# Version_2.net
KiCad netlist of a schematic drawn in EAGLE
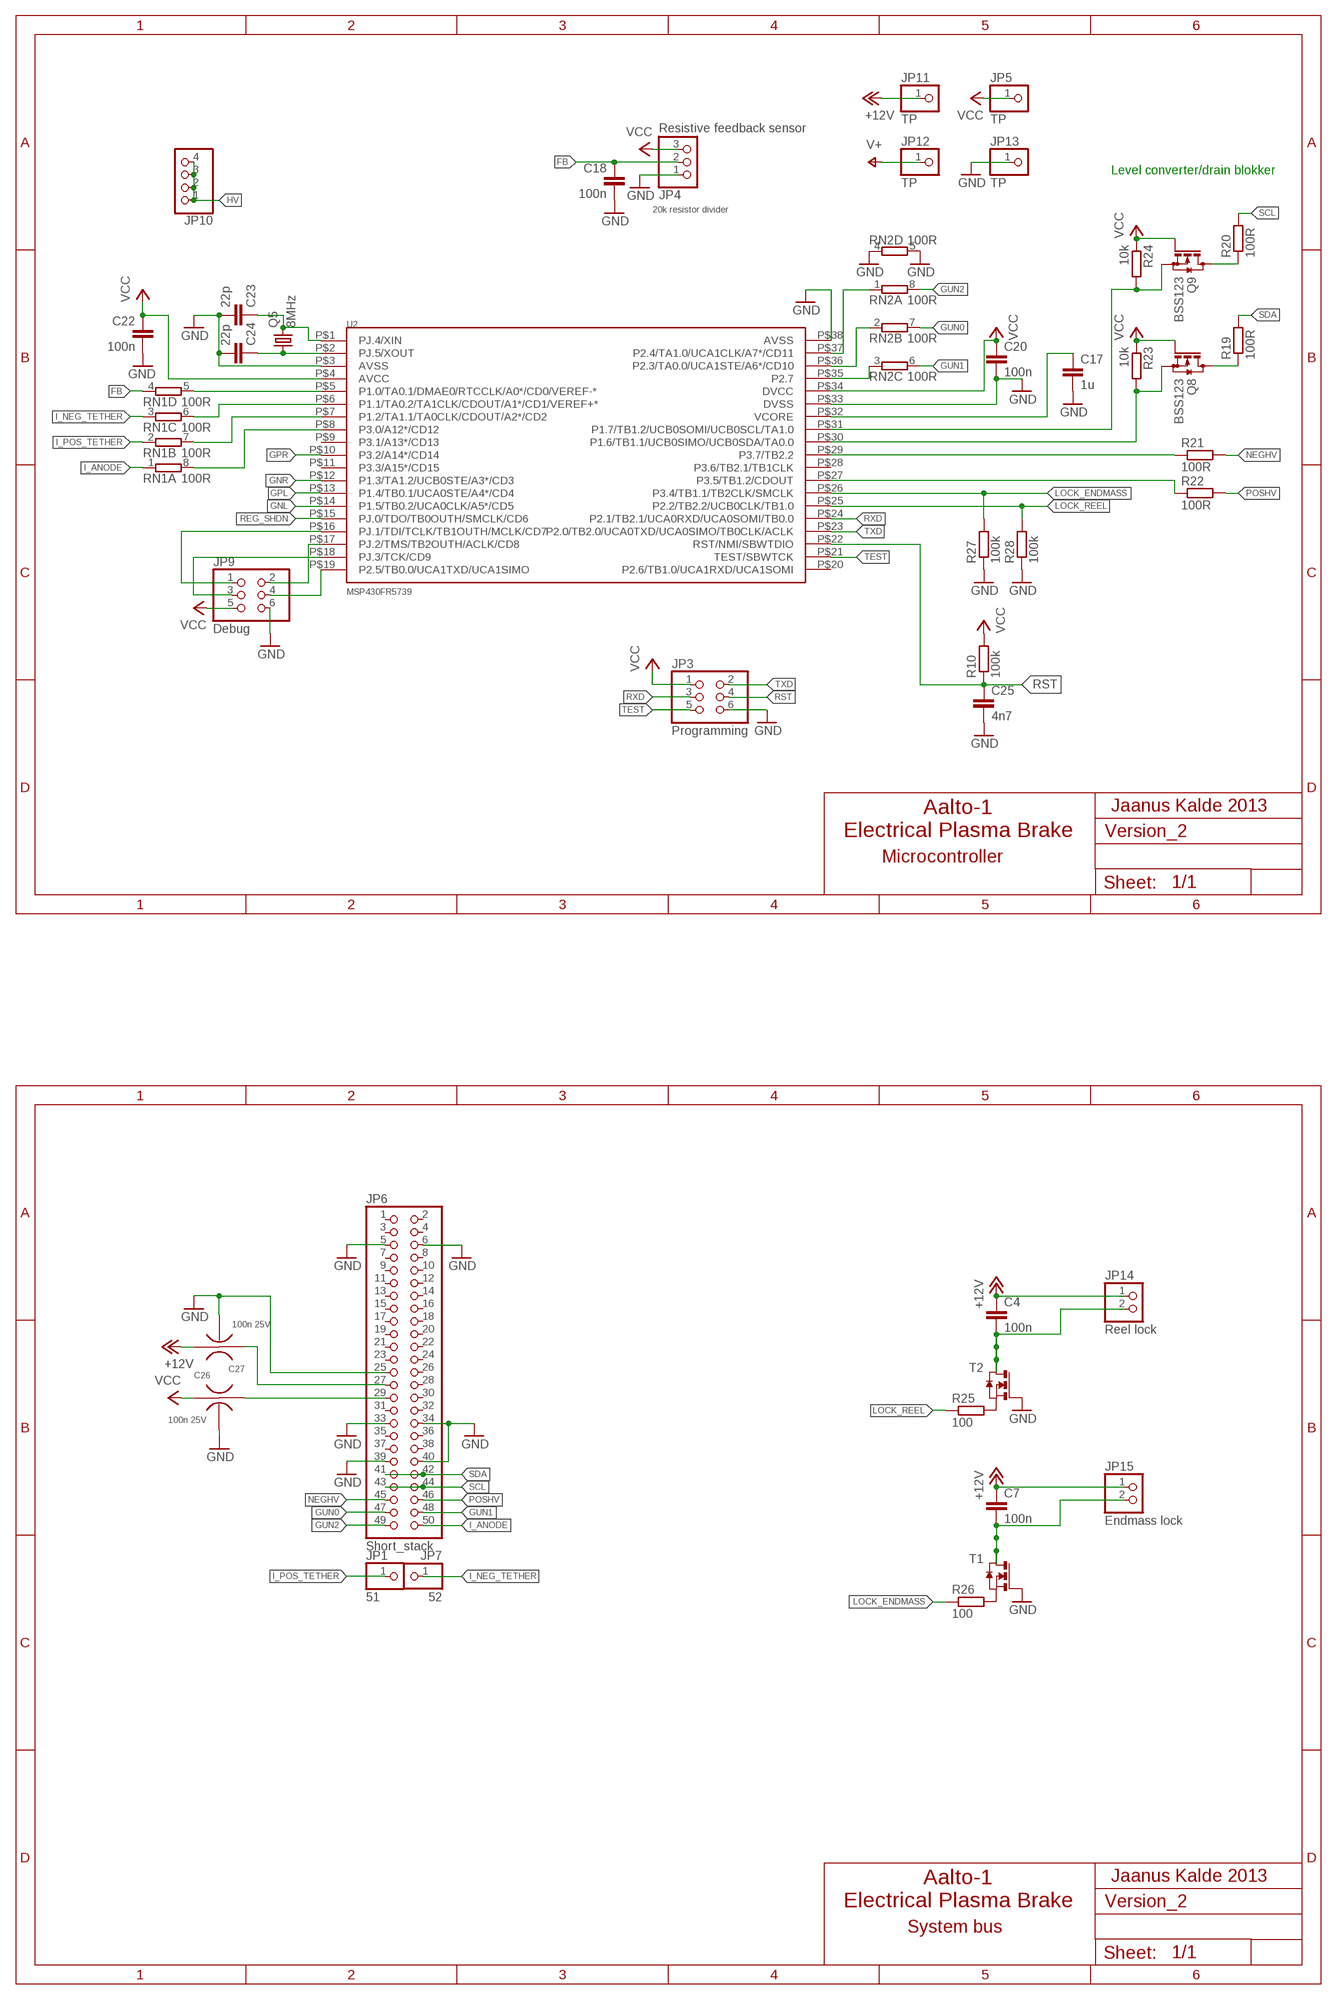
[diagram p0: schematic, sheet 1, part 1 of 2]
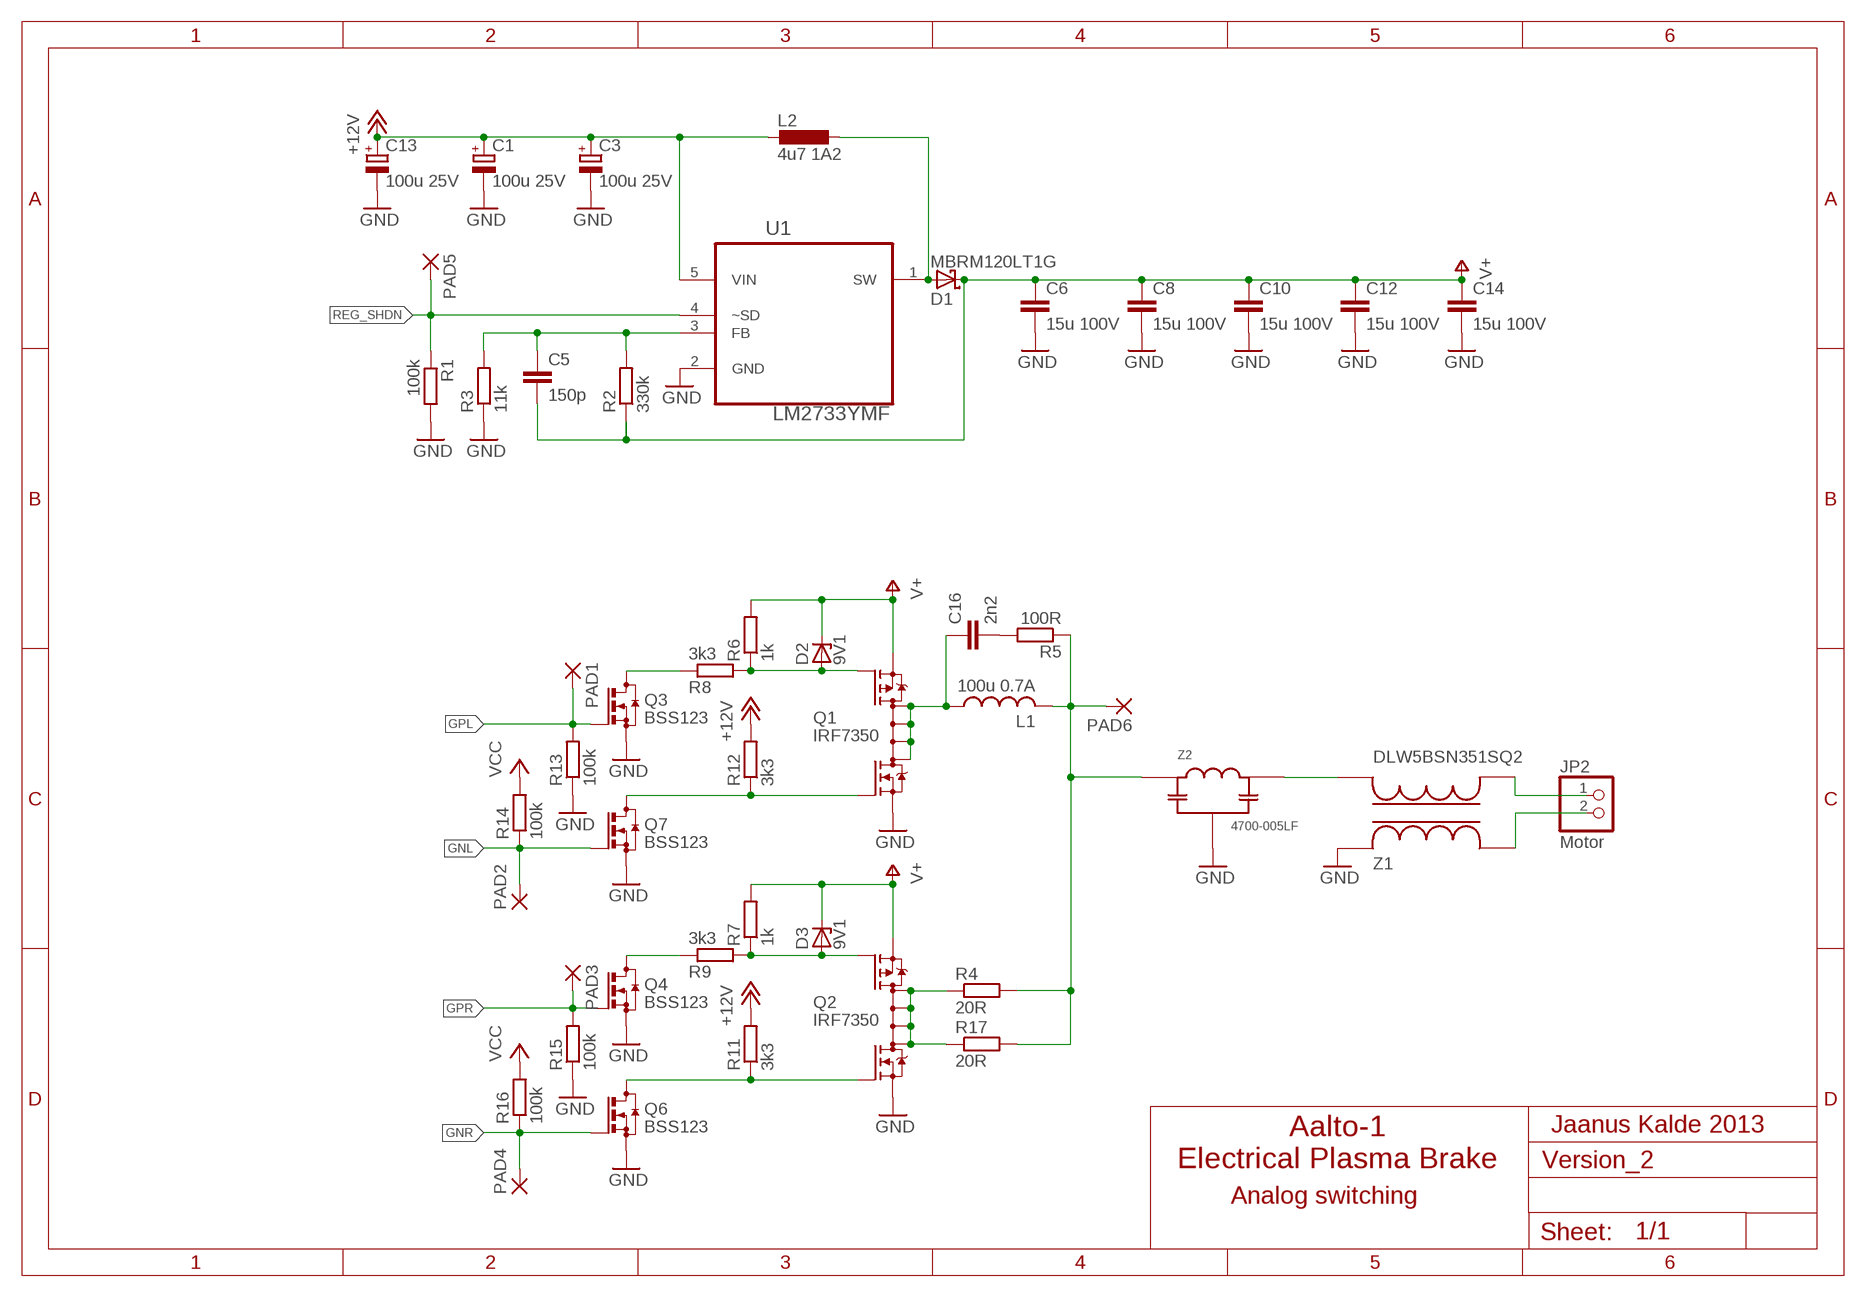
[diagram p1: schematic, sheet 1, part 2 of 2]

(export (version "E")
  (design (tool "Eeschema 10.0.6"))
  (components
    (comp (ref "C1")
      (value "100u 25V")
      (footprint "eagle-import:SMC_E")
      (libsource (lib "eagle-import") (part "CPOL-EUSMCE"))
    )
    (comp (ref "C3")
      (value "100u 25V")
      (footprint "eagle-import:SMC_E")
      (libsource (lib "eagle-import") (part "CPOL-EUSMCE"))
    )
    (comp (ref "C4")
      (value "100n")
      (footprint "eagle-import:C0603")
      (libsource (lib "eagle-import") (part "C-EUC0603"))
    )
    (comp (ref "C5")
      (value "150p")
      (footprint "eagle-import:C0603K")
      (libsource (lib "eagle-import") (part "C-EUC0603K"))
    )
    (comp (ref "C6")
      (value "15u 100V")
      (footprint "eagle-import:C2220K")
      (libsource (lib "eagle-import") (part "C-EUC2220K"))
    )
    (comp (ref "C7")
      (value "100n")
      (footprint "eagle-import:C0603")
      (libsource (lib "eagle-import") (part "C-EUC0603"))
    )
    (comp (ref "C8")
      (value "15u 100V")
      (footprint "eagle-import:C2220K")
      (libsource (lib "eagle-import") (part "C-EUC2220K"))
    )
    (comp (ref "C10")
      (value "15u 100V")
      (footprint "eagle-import:C2220K")
      (libsource (lib "eagle-import") (part "C-EUC2220K"))
    )
    (comp (ref "C12")
      (value "15u 100V")
      (footprint "eagle-import:C2220K")
      (libsource (lib "eagle-import") (part "C-EUC2220K"))
    )
    (comp (ref "C13")
      (value "100u 25V")
      (footprint "eagle-import:SMC_E")
      (libsource (lib "eagle-import") (part "CPOL-EUSMCE"))
    )
    (comp (ref "C14")
      (value "15u 100V")
      (footprint "eagle-import:C2220K")
      (libsource (lib "eagle-import") (part "C-EUC2220K"))
    )
    (comp (ref "C16")
      (value "2n2")
      (footprint "eagle-import:C0805")
      (libsource (lib "eagle-import") (part "C-EUC0805"))
    )
    (comp (ref "C17")
      (value "1u")
      (footprint "eagle-import:C0603K")
      (libsource (lib "eagle-import") (part "C-EUC0603K"))
    )
    (comp (ref "C18")
      (value "100n")
      (footprint "eagle-import:C0603K")
      (libsource (lib "eagle-import") (part "C-EUC0603K"))
    )
    (comp (ref "C20")
      (value "100n")
      (footprint "eagle-import:C0603K")
      (libsource (lib "eagle-import") (part "C-EUC0603K"))
    )
    (comp (ref "C22")
      (value "100n")
      (footprint "eagle-import:C0603")
      (libsource (lib "eagle-import") (part "C-EUC0603"))
    )
    (comp (ref "C23")
      (value "22p")
      (footprint "eagle-import:C0603")
      (libsource (lib "eagle-import") (part "C-EUC0603"))
    )
    (comp (ref "C24")
      (value "22p")
      (footprint "eagle-import:C0603")
      (libsource (lib "eagle-import") (part "C-EUC0603"))
    )
    (comp (ref "C25")
      (value "4n7")
      (footprint "eagle-import:C0603")
      (libsource (lib "eagle-import") (part "C-EUC0603"))
    )
    (comp (ref "C26")
      (value "100n 25V")
      (footprint "eagle-import:0805-3TERM")
      (libsource (lib "eagle-import") (part "CAP-3TERM"))
    )
    (comp (ref "C27")
      (value "100n 25V")
      (footprint "eagle-import:0805-3TERM")
      (libsource (lib "eagle-import") (part "CAP-3TERM"))
    )
    (comp (ref "D1")
      (value "MBRM120LT1G")
      (footprint "eagle-import:POWERMITE")
      (libsource (lib "eagle-import") (part "MBRM120LT1G"))
    )
    (comp (ref "D2")
      (value "9V1")
      (footprint "eagle-import:SOD80C")
      (libsource (lib "eagle-import") (part "ZENER-DIODESOD80C"))
    )
    (comp (ref "D3")
      (value "9V1")
      (footprint "eagle-import:SOD80C")
      (libsource (lib "eagle-import") (part "ZENER-DIODESOD80C"))
    )
    (comp (ref "JP1")
      (value "51")
      (footprint "eagle-import:1X01")
      (libsource (lib "eagle-import") (part "PINHD-1X1"))
    )
    (comp (ref "JP2")
      (value "Motor")
      (footprint "eagle-import:1X02M")
      (libsource (lib "eagle-import") (part "PINHD-1X02_2.00"))
    )
    (comp (ref "JP3")
      (value "Programming")
      (footprint "eagle-import:MICROMATCH-6")
      (libsource (lib "eagle-import") (part "PINHD-2X03_MICROMATCH"))
    )
    (comp (ref "JP4")
      (value "Resistive feedback sensor")
      (footprint "eagle-import:1X03M")
      (libsource (lib "eagle-import") (part "PINHD-1X03_2.00"))
    )
    (comp (ref "JP5")
      (value "TP")
      (footprint "eagle-import:1X01")
      (libsource (lib "eagle-import") (part "PINHD-1X1"))
    )
    (comp (ref "JP6")
      (value "Short_stack")
      (footprint "eagle-import:2X25")
      (libsource (lib "eagle-import") (part "PINHD-2X25"))
    )
    (comp (ref "JP7")
      (value "52")
      (footprint "eagle-import:1X01")
      (libsource (lib "eagle-import") (part "PINHD-1X1"))
    )
    (comp (ref "JP9")
      (value "Debug")
      (footprint "eagle-import:MICROMATCH-6")
      (libsource (lib "eagle-import") (part "PINHD-2X03_MICROMATCH"))
    )
    (comp (ref "JP10")
      (value "PINHD-1X4")
      (footprint "eagle-import:1X04")
      (libsource (lib "eagle-import") (part "PINHD-1X4"))
    )
    (comp (ref "JP11")
      (value "TP")
      (footprint "eagle-import:1X01")
      (libsource (lib "eagle-import") (part "PINHD-1X1"))
    )
    (comp (ref "JP12")
      (value "TP")
      (footprint "eagle-import:1X01")
      (libsource (lib "eagle-import") (part "PINHD-1X1"))
    )
    (comp (ref "JP13")
      (value "TP")
      (footprint "eagle-import:1X01")
      (libsource (lib "eagle-import") (part "PINHD-1X1"))
    )
    (comp (ref "JP14")
      (value "Reel lock")
      (footprint "eagle-import:1X02M")
      (libsource (lib "eagle-import") (part "PINHD-1X02_2.00"))
    )
    (comp (ref "JP15")
      (value "Endmass lock")
      (footprint "eagle-import:1X02M")
      (libsource (lib "eagle-import") (part "PINHD-1X02_2.00"))
    )
    (comp (ref "L1")
      (value "100u 0.7A")
      (footprint "eagle-import:L-SMD-7.3")
      (libsource (lib "eagle-import") (part "L-SMD-7.3"))
    )
    (comp (ref "L2")
      (value "4u7 1A2")
      (footprint "eagle-import:SRR4011")
      (libsource (lib "eagle-import") (part "SRR4011"))
    )
    (comp (ref "PAD1")
      (value "WIREPAD1,6/0,8")
      (footprint "eagle-import:1,6_0,8")
      (libsource (lib "eagle-import") (part "WIREPAD1,6/0,8"))
    )
    (comp (ref "PAD2")
      (value "WIREPAD1,6/0,8")
      (footprint "eagle-import:1,6_0,8")
      (libsource (lib "eagle-import") (part "WIREPAD1,6/0,8"))
    )
    (comp (ref "PAD3")
      (value "WIREPAD1,6/0,8")
      (footprint "eagle-import:1,6_0,8")
      (libsource (lib "eagle-import") (part "WIREPAD1,6/0,8"))
    )
    (comp (ref "PAD4")
      (value "WIREPAD1,6/0,8")
      (footprint "eagle-import:1,6_0,8")
      (libsource (lib "eagle-import") (part "WIREPAD1,6/0,8"))
    )
    (comp (ref "PAD5")
      (value "WIREPAD1,6/0,8")
      (footprint "eagle-import:1,6_0,8")
      (libsource (lib "eagle-import") (part "WIREPAD1,6/0,8"))
    )
    (comp (ref "PAD6")
      (value "WIREPAD1,6/0,8")
      (footprint "eagle-import:1,6_0,8")
      (libsource (lib "eagle-import") (part "WIREPAD1,6/0,8"))
    )
    (comp (ref "Q1")
      (value "IRF7350")
      (footprint "eagle-import:SO08-IRF")
      (libsource (lib "eagle-import") (part "IRF7389"))
    )
    (comp (ref "Q2")
      (value "IRF7350")
      (footprint "eagle-import:SO08-IRF")
      (libsource (lib "eagle-import") (part "IRF7389"))
    )
    (comp (ref "Q3")
      (value "BSS123")
      (footprint "eagle-import:SOT23")
      (libsource (lib "eagle-import") (part "BSS123"))
    )
    (comp (ref "Q4")
      (value "BSS123")
      (footprint "eagle-import:SOT23")
      (libsource (lib "eagle-import") (part "BSS123"))
    )
    (comp (ref "Q5")
      (value "8MHz")
      (footprint "eagle-import:HC49U-V")
      (libsource (lib "eagle-import") (part "CRYSTALHC49UV"))
    )
    (comp (ref "Q6")
      (value "BSS123")
      (footprint "eagle-import:SOT23")
      (libsource (lib "eagle-import") (part "BSS123"))
    )
    (comp (ref "Q7")
      (value "BSS123")
      (footprint "eagle-import:SOT23")
      (libsource (lib "eagle-import") (part "BSS123"))
    )
    (comp (ref "Q8")
      (value "BSS123")
      (footprint "eagle-import:SOT23")
      (libsource (lib "eagle-import") (part "BSS123"))
    )
    (comp (ref "Q9")
      (value "BSS123")
      (footprint "eagle-import:SOT23")
      (libsource (lib "eagle-import") (part "BSS123"))
    )
    (comp (ref "R1")
      (value "100k")
      (footprint "eagle-import:R0603")
      (libsource (lib "eagle-import") (part "R-EU_R0603"))
    )
    (comp (ref "R2")
      (value "330k")
      (footprint "eagle-import:R0603")
      (libsource (lib "eagle-import") (part "R-EU_R0603"))
    )
    (comp (ref "R3")
      (value "11k")
      (footprint "eagle-import:R0603")
      (libsource (lib "eagle-import") (part "R-EU_R0603"))
    )
    (comp (ref "R4")
      (value "20R")
      (footprint "eagle-import:R2512")
      (libsource (lib "eagle-import") (part "R-EU_R2512"))
    )
    (comp (ref "R5")
      (value "100R")
      (footprint "eagle-import:R0805")
      (libsource (lib "eagle-import") (part "R-EU_R0805"))
    )
    (comp (ref "R6")
      (value "1k")
      (footprint "eagle-import:R0805")
      (libsource (lib "eagle-import") (part "R-EU_R0805"))
    )
    (comp (ref "R7")
      (value "1k")
      (footprint "eagle-import:R0805")
      (libsource (lib "eagle-import") (part "R-EU_R0805"))
    )
    (comp (ref "R8")
      (value "3k3")
      (footprint "eagle-import:R0805")
      (libsource (lib "eagle-import") (part "R-EU_R0805"))
    )
    (comp (ref "R9")
      (value "3k3")
      (footprint "eagle-import:R0805")
      (libsource (lib "eagle-import") (part "R-EU_R0805"))
    )
    (comp (ref "R10")
      (value "100k")
      (footprint "eagle-import:R0603")
      (libsource (lib "eagle-import") (part "R-EU_R0603"))
    )
    (comp (ref "R11")
      (value "3k3")
      (footprint "eagle-import:R0805")
      (libsource (lib "eagle-import") (part "R-EU_R0805"))
    )
    (comp (ref "R12")
      (value "3k3")
      (footprint "eagle-import:R0805")
      (libsource (lib "eagle-import") (part "R-EU_R0805"))
    )
    (comp (ref "R13")
      (value "100k")
      (footprint "eagle-import:R0603")
      (libsource (lib "eagle-import") (part "R-EU_R0603"))
    )
    (comp (ref "R14")
      (value "100k")
      (footprint "eagle-import:R0603")
      (libsource (lib "eagle-import") (part "R-EU_R0603"))
    )
    (comp (ref "R15")
      (value "100k")
      (footprint "eagle-import:R0603")
      (libsource (lib "eagle-import") (part "R-EU_R0603"))
    )
    (comp (ref "R16")
      (value "100k")
      (footprint "eagle-import:R0603")
      (libsource (lib "eagle-import") (part "R-EU_R0603"))
    )
    (comp (ref "R17")
      (value "20R")
      (footprint "eagle-import:R2512")
      (libsource (lib "eagle-import") (part "R-EU_R2512"))
    )
    (comp (ref "R19")
      (value "100R")
      (footprint "eagle-import:R0603")
      (libsource (lib "eagle-import") (part "R-EU_R0603"))
    )
    (comp (ref "R20")
      (value "100R")
      (footprint "eagle-import:R0603")
      (libsource (lib "eagle-import") (part "R-EU_R0603"))
    )
    (comp (ref "R21")
      (value "100R")
      (footprint "eagle-import:R0603")
      (libsource (lib "eagle-import") (part "R-EU_R0603"))
    )
    (comp (ref "R22")
      (value "100R")
      (footprint "eagle-import:R0603")
      (libsource (lib "eagle-import") (part "R-EU_R0603"))
    )
    (comp (ref "R23")
      (value "10k")
      (footprint "eagle-import:R0603")
      (libsource (lib "eagle-import") (part "R-EU_R0603"))
    )
    (comp (ref "R24")
      (value "10k")
      (footprint "eagle-import:R0603")
      (libsource (lib "eagle-import") (part "R-EU_R0603"))
    )
    (comp (ref "R25")
      (value "100")
      (footprint "eagle-import:R0603")
      (libsource (lib "eagle-import") (part "R-EU_R0603"))
    )
    (comp (ref "R26")
      (value "100")
      (footprint "eagle-import:R0603")
      (libsource (lib "eagle-import") (part "R-EU_R0603"))
    )
    (comp (ref "R27")
      (value "100k")
      (footprint "eagle-import:R0603")
      (libsource (lib "eagle-import") (part "R-EU_R0603"))
    )
    (comp (ref "R28")
      (value "100k")
      (footprint "eagle-import:R0603")
      (libsource (lib "eagle-import") (part "R-EU_R0603"))
    )
    (comp (ref "RN1")
      (value "100R")
      (footprint "eagle-import:EXBN8V")
      (fields (field (name "OC_FARNELL") "unknown") (field (name "OC_NEWARK") "unknown"))
      (libsource (lib "eagle-import") (part "4R-NEXBN8V"))
    )
    (comp (ref "RN2")
      (value "100R")
      (footprint "eagle-import:EXBN8V")
      (libsource (lib "eagle-import") (part "4R-NEXBN8V"))
    )
    (comp (ref "T1")
      (value "NMOSSOT23-6")
      (footprint "eagle-import:SOT23-6")
      (libsource (lib "eagle-import") (part "NMOSSOT23-6"))
    )
    (comp (ref "T2")
      (value "NMOSSOT23-6")
      (footprint "eagle-import:SOT23-6")
      (fields (field (name "OC_FARNELL") "unknown") (field (name "OC_NEWARK") "unknown"))
      (libsource (lib "eagle-import") (part "NMOSSOT23-6"))
    )
    (comp (ref "U1")
      (value "LM2733YMF")
      (footprint "eagle-import:SOT95P284X119-5N")
      (libsource (lib "eagle-import") (part "LM2733YMF"))
    )
    (comp (ref "U2")
      (value "MSP430FR5739")
      (footprint "eagle-import:TSSOP38")
      (libsource (lib "eagle-import") (part "MSP430FR5739"))
    )
    (comp (ref "Z1")
      (value "DLW5BSN351SQ2")
      (footprint "eagle-import:DLW5BS")
      (libsource (lib "eagle-import") (part "DLW5BS"))
    )
    (comp (ref "Z2")
      (value "4700-005LF")
      (footprint "eagle-import:FILTER-PI")
      (libsource (lib "eagle-import") (part "FILTER-PI"))
    )
  )
  (nets
    (net (code "1") (name "+12V") (class "Default")
      (node (ref "C1") (pin "+") (pinfunction "+_+") (pintype "passive"))
      (node (ref "C13") (pin "+") (pinfunction "+_+") (pintype "passive"))
      (node (ref "C26") (pin "P$1") (pinfunction "P$1_P$1") (pintype "bidirectional"))
      (node (ref "C3") (pin "+") (pinfunction "+_+") (pintype "passive"))
      (node (ref "C4") (pin "1") (pinfunction "1_1") (pintype "passive"))
      (node (ref "C7") (pin "1") (pinfunction "1_1") (pintype "passive"))
      (node (ref "JP11") (pin "1") (pinfunction "1_1") (pintype "passive"))
      (node (ref "JP14") (pin "1") (pinfunction "1_1") (pintype "passive"))
      (node (ref "JP15") (pin "1") (pinfunction "1_1") (pintype "passive"))
      (node (ref "L2") (pin "P$1") (pinfunction "1_P$1") (pintype "passive"))
      (node (ref "R11") (pin "2") (pinfunction "2_2") (pintype "passive"))
      (node (ref "R12") (pin "2") (pinfunction "2_2") (pintype "passive"))
      (node (ref "U1") (pin "5") (pinfunction "VIN_5") (pintype "power_in"))
    )
    (net (code "2") (name "FB") (class "Default")
      (node (ref "C18") (pin "1") (pinfunction "1_1") (pintype "passive"))
      (node (ref "JP4") (pin "2") (pinfunction "2_2") (pintype "passive"))
      (node (ref "RN1") (pin "4") (pinfunction "1_4") (pintype "passive"))
    )
    (net (code "3") (name "GND") (class "Default")
      (node (ref "C1") (pin "-") (pinfunction "-_-") (pintype "passive"))
      (node (ref "C10") (pin "2") (pinfunction "2_2") (pintype "passive"))
      (node (ref "C12") (pin "2") (pinfunction "2_2") (pintype "passive"))
      (node (ref "C13") (pin "-") (pinfunction "-_-") (pintype "passive"))
      (node (ref "C14") (pin "2") (pinfunction "2_2") (pintype "passive"))
      (node (ref "C17") (pin "2") (pinfunction "2_2") (pintype "passive"))
      (node (ref "C18") (pin "2") (pinfunction "2_2") (pintype "passive"))
      (node (ref "C20") (pin "2") (pinfunction "2_2") (pintype "passive"))
      (node (ref "C22") (pin "2") (pinfunction "2_2") (pintype "passive"))
      (node (ref "C23") (pin "2") (pinfunction "2_2") (pintype "passive"))
      (node (ref "C24") (pin "2") (pinfunction "2_2") (pintype "passive"))
      (node (ref "C25") (pin "2") (pinfunction "2_2") (pintype "passive"))
      (node (ref "C26") (pin "P$2") (pinfunction "P$2_P$2") (pintype "bidirectional"))
      (node (ref "C27") (pin "P$2") (pinfunction "P$2_P$2") (pintype "bidirectional"))
      (node (ref "C3") (pin "-") (pinfunction "-_-") (pintype "passive"))
      (node (ref "C6") (pin "2") (pinfunction "2_2") (pintype "passive"))
      (node (ref "C8") (pin "2") (pinfunction "2_2") (pintype "passive"))
      (node (ref "JP13") (pin "1") (pinfunction "1_1") (pintype "passive"))
      (node (ref "JP3") (pin "6") (pinfunction "6_6") (pintype "passive"))
      (node (ref "JP4") (pin "1") (pinfunction "1_1") (pintype "passive"))
      (node (ref "JP6") (pin "25") (pinfunction "25_25") (pintype "passive"))
      (node (ref "JP6") (pin "33") (pinfunction "33_33") (pintype "passive"))
      (node (ref "JP6") (pin "34") (pinfunction "34_34") (pintype "passive"))
      (node (ref "JP6") (pin "39") (pinfunction "39_39") (pintype "passive"))
      (node (ref "JP6") (pin "40") (pinfunction "40_40") (pintype "passive"))
      (node (ref "JP6") (pin "5") (pinfunction "5_5") (pintype "passive"))
      (node (ref "JP6") (pin "6") (pinfunction "6_6") (pintype "passive"))
      (node (ref "JP9") (pin "6") (pinfunction "6_6") (pintype "passive"))
      (node (ref "Q1") (pin "1") (pinfunction "N-S_1") (pintype "passive"))
      (node (ref "Q2") (pin "1") (pinfunction "N-S_1") (pintype "passive"))
      (node (ref "Q3") (pin "2") (pinfunction "S_2") (pintype "passive"))
      (node (ref "Q4") (pin "2") (pinfunction "S_2") (pintype "passive"))
      (node (ref "Q6") (pin "2") (pinfunction "S_2") (pintype "passive"))
      (node (ref "Q7") (pin "2") (pinfunction "S_2") (pintype "passive"))
      (node (ref "R1") (pin "2") (pinfunction "2_2") (pintype "passive"))
      (node (ref "R13") (pin "1") (pinfunction "1_1") (pintype "passive"))
      (node (ref "R15") (pin "1") (pinfunction "1_1") (pintype "passive"))
      (node (ref "R27") (pin "1") (pinfunction "1_1") (pintype "passive"))
      (node (ref "R28") (pin "1") (pinfunction "1_1") (pintype "passive"))
      (node (ref "R3") (pin "1") (pinfunction "1_1") (pintype "passive"))
      (node (ref "RN2") (pin "4") (pinfunction "1_4") (pintype "passive"))
      (node (ref "RN2") (pin "5") (pinfunction "2_5") (pintype "passive"))
      (node (ref "T1") (pin "4") (pinfunction "G_4") (pintype "passive"))
      (node (ref "T2") (pin "4") (pinfunction "G_4") (pintype "passive"))
      (node (ref "U1") (pin "2") (pinfunction "GND_2") (pintype "passive"))
      (node (ref "U2") (pin "P$3") (pinfunction "AVSS_P$3") (pintype "bidirectional"))
      (node (ref "U2") (pin "P$33") (pinfunction "DVSS_P$33") (pintype "bidirectional"))
      (node (ref "U2") (pin "P$38") (pinfunction "AVSS_P$38") (pintype "bidirectional"))
      (node (ref "Z1") (pin "P$2") (pinfunction "P$1_P$2") (pintype "bidirectional"))
      (node (ref "Z2") (pin "P$2") (pinfunction "P$3_P$2") (pintype "bidirectional"))
    )
    (net (code "4") (name "GNL") (class "Default")
      (node (ref "PAD2") (pin "1") (pinfunction "P_1") (pintype "passive"))
      (node (ref "Q7") (pin "1") (pinfunction "G_1") (pintype "passive"))
      (node (ref "R14") (pin "1") (pinfunction "1_1") (pintype "passive"))
      (node (ref "U2") (pin "P$14") (pinfunction "P1.5/TB0.2/UCA0CLK/A5*/CD5_P$14") (pintype "bidirectional"))
    )
    (net (code "5") (name "GNR") (class "Default")
      (node (ref "PAD4") (pin "1") (pinfunction "P_1") (pintype "passive"))
      (node (ref "Q6") (pin "1") (pinfunction "G_1") (pintype "passive"))
      (node (ref "R16") (pin "1") (pinfunction "1_1") (pintype "passive"))
      (node (ref "U2") (pin "P$12") (pinfunction "P1.3/TA1.2/UCB0STE/A3*/CD3_P$12") (pintype "bidirectional"))
    )
    (net (code "6") (name "GPL") (class "Default")
      (node (ref "PAD1") (pin "1") (pinfunction "P_1") (pintype "passive"))
      (node (ref "Q3") (pin "1") (pinfunction "G_1") (pintype "passive"))
      (node (ref "R13") (pin "2") (pinfunction "2_2") (pintype "passive"))
      (node (ref "U2") (pin "P$13") (pinfunction "P1.4/TB0.1/UCA0STE/A4*/CD4_P$13") (pintype "bidirectional"))
    )
    (net (code "7") (name "GPR") (class "Default")
      (node (ref "PAD3") (pin "1") (pinfunction "P_1") (pintype "passive"))
      (node (ref "Q4") (pin "1") (pinfunction "G_1") (pintype "passive"))
      (node (ref "R15") (pin "2") (pinfunction "2_2") (pintype "passive"))
      (node (ref "U2") (pin "P$10") (pinfunction "P3.2/A14*/CD14_P$10") (pintype "bidirectional"))
    )
    (net (code "8") (name "GUN0") (class "Default")
      (node (ref "JP6") (pin "47") (pinfunction "47_47") (pintype "passive"))
      (node (ref "RN2") (pin "7") (pinfunction "2_7") (pintype "passive"))
    )
    (net (code "9") (name "GUN1") (class "Default")
      (node (ref "JP6") (pin "48") (pinfunction "48_48") (pintype "passive"))
      (node (ref "RN2") (pin "6") (pinfunction "2_6") (pintype "passive"))
    )
    (net (code "10") (name "GUN2") (class "Default")
      (node (ref "JP6") (pin "49") (pinfunction "49_49") (pintype "passive"))
      (node (ref "RN2") (pin "8") (pinfunction "2_8") (pintype "passive"))
    )
    (net (code "11") (name "HV") (class "Default")
      (node (ref "JP10") (pin "1") (pinfunction "1_1") (pintype "passive"))
      (node (ref "JP10") (pin "2") (pinfunction "2_2") (pintype "passive"))
      (node (ref "JP10") (pin "3") (pinfunction "3_3") (pintype "passive"))
      (node (ref "JP10") (pin "4") (pinfunction "4_4") (pintype "passive"))
    )
    (net (code "12") (name "I_ANODE") (class "Default")
      (node (ref "JP6") (pin "50") (pinfunction "50_50") (pintype "passive"))
      (node (ref "RN1") (pin "1") (pinfunction "1_1") (pintype "passive"))
    )
    (net (code "13") (name "I_NEG_TETHER") (class "Default")
      (node (ref "JP7") (pin "1") (pinfunction "1_1") (pintype "passive"))
      (node (ref "RN1") (pin "3") (pinfunction "1_3") (pintype "passive"))
    )
    (net (code "14") (name "I_POS_TETHER") (class "Default")
      (node (ref "JP1") (pin "1") (pinfunction "1_1") (pintype "passive"))
      (node (ref "RN1") (pin "2") (pinfunction "1_2") (pintype "passive"))
    )
    (net (code "15") (name "LOCK_ENDMASS") (class "Default")
      (node (ref "R26") (pin "1") (pinfunction "1_1") (pintype "passive"))
      (node (ref "R27") (pin "2") (pinfunction "2_2") (pintype "passive"))
      (node (ref "U2") (pin "P$26") (pinfunction "P3.4/TB1.1/TB2CLK/SMCLK_P$26") (pintype "bidirectional"))
    )
    (net (code "16") (name "LOCK_REEL") (class "Default")
      (node (ref "R25") (pin "1") (pinfunction "1_1") (pintype "passive"))
      (node (ref "R28") (pin "2") (pinfunction "2_2") (pintype "passive"))
      (node (ref "U2") (pin "P$25") (pinfunction "P2.2/TB2.2/UCB0CLK/TB1.0_P$25") (pintype "bidirectional"))
    )
    (net (code "17") (name "NEGHV") (class "Default")
      (node (ref "JP6") (pin "45") (pinfunction "45_45") (pintype "passive"))
      (node (ref "R21") (pin "2") (pinfunction "2_2") (pintype "passive"))
    )
    (net (code "18") (name "Net-(C16-Pad2)") (class "Default")
      (node (ref "C16") (pin "2") (pinfunction "2_2") (pintype "passive"))
      (node (ref "R5") (pin "2") (pinfunction "2_2") (pintype "passive"))
    )
    (net (code "19") (name "Net-(C26-PadP$3)") (class "Default")
      (node (ref "C26") (pin "P$3") (pinfunction "P$3_P$3") (pintype "bidirectional"))
      (node (ref "JP6") (pin "27") (pinfunction "27_27") (pintype "passive"))
    )
    (net (code "20") (name "Net-(C27-PadP$1)") (class "Default")
      (node (ref "C27") (pin "P$1") (pinfunction "P$1_P$1") (pintype "bidirectional"))
      (node (ref "JP6") (pin "29") (pinfunction "29_29") (pintype "passive"))
    )
    (net (code "21") (name "Net-(D1-A)") (class "Default")
      (node (ref "D1") (pin "2") (pinfunction "A_2") (pintype "passive"))
      (node (ref "L2") (pin "P$2") (pinfunction "2_P$2") (pintype "passive"))
      (node (ref "U1") (pin "1") (pinfunction "SW_1") (pintype "output"))
    )
    (net (code "22") (name "Net-(JP2-Pad1)") (class "Default")
      (node (ref "JP2") (pin "1") (pinfunction "1_1") (pintype "passive"))
      (node (ref "Z1") (pin "P$4") (pinfunction "P$4_P$4") (pintype "bidirectional"))
    )
    (net (code "23") (name "Net-(L1-1)") (class "Default")
      (node (ref "C16") (pin "1") (pinfunction "1_1") (pintype "passive"))
      (node (ref "L1") (pin "P$1") (pinfunction "1_P$1") (pintype "passive"))
      (node (ref "Q1") (pin "5") (pinfunction "D_5") (pintype "passive"))
      (node (ref "Q1") (pin "6") (pinfunction "D_6") (pintype "passive"))
      (node (ref "Q1") (pin "7") (pinfunction "D_7") (pintype "passive"))
      (node (ref "Q1") (pin "8") (pinfunction "D_8") (pintype "passive"))
    )
    (net (code "24") (name "Net-(L1-2)") (class "Default")
      (node (ref "L1") (pin "P$2") (pinfunction "2_P$2") (pintype "passive"))
      (node (ref "PAD6") (pin "1") (pinfunction "P_1") (pintype "passive"))
      (node (ref "R17") (pin "2") (pinfunction "2_2") (pintype "passive"))
      (node (ref "R4") (pin "2") (pinfunction "2_2") (pintype "passive"))
      (node (ref "R5") (pin "1") (pinfunction "1_1") (pintype "passive"))
      (node (ref "Z2") (pin "P$1") (pinfunction "P$1_P$1") (pintype "bidirectional"))
    )
    (net (code "25") (name "Net-(Q1-N-G)") (class "Default")
      (node (ref "Q1") (pin "2") (pinfunction "N-G_2") (pintype "passive"))
      (node (ref "Q7") (pin "3") (pinfunction "D_3") (pintype "passive"))
      (node (ref "R12") (pin "1") (pinfunction "1_1") (pintype "passive"))
    )
    (net (code "26") (name "Net-(Q1-P-G)") (class "Default")
      (node (ref "D2") (pin "A") (pinfunction "A_A") (pintype "passive"))
      (node (ref "Q1") (pin "4") (pinfunction "P-G_4") (pintype "passive"))
      (node (ref "R6") (pin "1") (pinfunction "1_1") (pintype "passive"))
      (node (ref "R8") (pin "2") (pinfunction "2_2") (pintype "passive"))
    )
    (net (code "27") (name "Net-(Q2-D-Pad5)") (class "Default")
      (node (ref "Q2") (pin "5") (pinfunction "D_5") (pintype "passive"))
      (node (ref "Q2") (pin "6") (pinfunction "D_6") (pintype "passive"))
      (node (ref "Q2") (pin "7") (pinfunction "D_7") (pintype "passive"))
      (node (ref "Q2") (pin "8") (pinfunction "D_8") (pintype "passive"))
      (node (ref "R17") (pin "1") (pinfunction "1_1") (pintype "passive"))
      (node (ref "R4") (pin "1") (pinfunction "1_1") (pintype "passive"))
    )
    (net (code "28") (name "Net-(Q2-N-G)") (class "Default")
      (node (ref "Q2") (pin "2") (pinfunction "N-G_2") (pintype "passive"))
      (node (ref "Q6") (pin "3") (pinfunction "D_3") (pintype "passive"))
      (node (ref "R11") (pin "1") (pinfunction "1_1") (pintype "passive"))
    )
    (net (code "29") (name "Net-(Q2-P-G)") (class "Default")
      (node (ref "D3") (pin "A") (pinfunction "A_A") (pintype "passive"))
      (node (ref "Q2") (pin "4") (pinfunction "P-G_4") (pintype "passive"))
      (node (ref "R7") (pin "1") (pinfunction "1_1") (pintype "passive"))
      (node (ref "R9") (pin "2") (pinfunction "2_2") (pintype "passive"))
    )
    (net (code "30") (name "Net-(Q3-D)") (class "Default")
      (node (ref "Q3") (pin "3") (pinfunction "D_3") (pintype "passive"))
      (node (ref "R8") (pin "1") (pinfunction "1_1") (pintype "passive"))
    )
    (net (code "31") (name "Net-(Q4-D)") (class "Default")
      (node (ref "Q4") (pin "3") (pinfunction "D_3") (pintype "passive"))
      (node (ref "R9") (pin "1") (pinfunction "1_1") (pintype "passive"))
    )
    (net (code "32") (name "Net-(Q8-D)") (class "Default")
      (node (ref "Q8") (pin "3") (pinfunction "D_3") (pintype "passive"))
      (node (ref "R19") (pin "1") (pinfunction "1_1") (pintype "passive"))
    )
    (net (code "33") (name "Net-(Q8-S)") (class "Default")
      (node (ref "Q8") (pin "2") (pinfunction "S_2") (pintype "passive"))
      (node (ref "R23") (pin "2") (pinfunction "2_2") (pintype "passive"))
      (node (ref "U2") (pin "P$30") (pinfunction "P1.6/TB1.1/UCB0SIMO/UCB0SDA/TA0.0_P$30") (pintype "bidirectional"))
    )
    (net (code "34") (name "Net-(Q9-D)") (class "Default")
      (node (ref "Q9") (pin "3") (pinfunction "D_3") (pintype "passive"))
      (node (ref "R20") (pin "1") (pinfunction "1_1") (pintype "passive"))
    )
    (net (code "35") (name "Net-(Q9-S)") (class "Default")
      (node (ref "Q9") (pin "2") (pinfunction "S_2") (pintype "passive"))
      (node (ref "R24") (pin "2") (pinfunction "2_2") (pintype "passive"))
      (node (ref "U2") (pin "P$31") (pinfunction "P1.7/TB1.2/UCB0SOMI/UCB0SCL/TA1.0_P$31") (pintype "bidirectional"))
    )
    (net (code "36") (name "Net-(RN1A-2)") (class "Default")
      (node (ref "RN1") (pin "8") (pinfunction "2_8") (pintype "passive"))
      (node (ref "U2") (pin "P$8") (pinfunction "P3.0/A12*/CD12_P$8") (pintype "bidirectional"))
    )
    (net (code "37") (name "Net-(RN1B-2)") (class "Default")
      (node (ref "RN1") (pin "7") (pinfunction "2_7") (pintype "passive"))
      (node (ref "U2") (pin "P$7") (pinfunction "P1.2/TA1.1/TA0CLK/CDOUT/A2*/CD2_P$7") (pintype "bidirectional"))
    )
    (net (code "38") (name "Net-(RN1C-2)") (class "Default")
      (node (ref "RN1") (pin "6") (pinfunction "2_6") (pintype "passive"))
      (node (ref "U2") (pin "P$6") (pinfunction "P1.1/TA0.2/TA1CLK/CDOUT/A1*/CD1/VEREF+*_P$6") (pintype "bidirectional"))
    )
    (net (code "39") (name "Net-(RN1D-2)") (class "Default")
      (node (ref "RN1") (pin "5") (pinfunction "2_5") (pintype "passive"))
      (node (ref "U2") (pin "P$5") (pinfunction "P1.0/TA0.1/DMAE0/RTCCLK/A0*/CD0/VEREF-*_P$5") (pintype "bidirectional"))
    )
    (net (code "40") (name "Net-(RN2B-1)") (class "Default")
      (node (ref "RN2") (pin "2") (pinfunction "1_2") (pintype "passive"))
      (node (ref "U2") (pin "P$36") (pinfunction "P2.3/TA0.0/UCA1STE/A6*/CD10_P$36") (pintype "bidirectional"))
    )
    (net (code "41") (name "Net-(RN2C-1)") (class "Default")
      (node (ref "RN2") (pin "3") (pinfunction "1_3") (pintype "passive"))
      (node (ref "U2") (pin "P$35") (pinfunction "P2.7_P$35") (pintype "bidirectional"))
    )
    (net (code "42") (name "Net-(T1-D)") (class "Default")
      (node (ref "C7") (pin "2") (pinfunction "2_2") (pintype "passive"))
      (node (ref "JP15") (pin "2") (pinfunction "2_2") (pintype "passive"))
      (node (ref "T1") (pin "1") (pinfunction "D_1") (pintype "passive"))
      (node (ref "T1") (pin "2") (pinfunction "D1_2") (pintype "passive"))
      (node (ref "T1") (pin "5") (pinfunction "D2_5") (pintype "passive"))
      (node (ref "T1") (pin "6") (pinfunction "D3_6") (pintype "passive"))
    )
    (net (code "43") (name "Net-(T1-S)") (class "Default")
      (node (ref "R26") (pin "2") (pinfunction "2_2") (pintype "passive"))
      (node (ref "T1") (pin "3") (pinfunction "S_3") (pintype "passive"))
    )
    (net (code "44") (name "Net-(T2-D)") (class "Default")
      (node (ref "C4") (pin "2") (pinfunction "2_2") (pintype "passive"))
      (node (ref "JP14") (pin "2") (pinfunction "2_2") (pintype "passive"))
      (node (ref "T2") (pin "1") (pinfunction "D_1") (pintype "passive"))
      (node (ref "T2") (pin "2") (pinfunction "D1_2") (pintype "passive"))
      (node (ref "T2") (pin "5") (pinfunction "D2_5") (pintype "passive"))
      (node (ref "T2") (pin "6") (pinfunction "D3_6") (pintype "passive"))
    )
    (net (code "45") (name "Net-(T2-S)") (class "Default")
      (node (ref "R25") (pin "2") (pinfunction "2_2") (pintype "passive"))
      (node (ref "T2") (pin "3") (pinfunction "S_3") (pintype "passive"))
    )
    (net (code "46") (name "Net-(U1-FB)") (class "Default")
      (node (ref "C5") (pin "1") (pinfunction "1_1") (pintype "passive"))
      (node (ref "R2") (pin "2") (pinfunction "2_2") (pintype "passive"))
      (node (ref "R3") (pin "2") (pinfunction "2_2") (pintype "passive"))
      (node (ref "U1") (pin "3") (pinfunction "FB_3") (pintype "input"))
    )
    (net (code "47") (name "Net-(U2-P2.4{slash}TA1.0{slash}UCA1CLK{slash}A7*{slash}CD11)") (class "Default")
      (node (ref "RN2") (pin "1") (pinfunction "1_1") (pintype "passive"))
      (node (ref "U2") (pin "P$37") (pinfunction "P2.4/TA1.0/UCA1CLK/A7*/CD11_P$37") (pintype "bidirectional"))
    )
    (net (code "48") (name "Net-(U2-P2.5{slash}TB0.0{slash}UCA1TXD{slash}UCA1SIMO)") (class "Default")
      (node (ref "JP9") (pin "4") (pinfunction "4_4") (pintype "passive"))
      (node (ref "U2") (pin "P$19") (pinfunction "P2.5/TB0.0/UCA1TXD/UCA1SIMO_P$19") (pintype "bidirectional"))
    )
    (net (code "49") (name "Net-(U2-P3.5{slash}TB1.2{slash}CDOUT)") (class "Default")
      (node (ref "R22") (pin "1") (pinfunction "1_1") (pintype "passive"))
      (node (ref "U2") (pin "P$27") (pinfunction "P3.5/TB1.2/CDOUT_P$27") (pintype "bidirectional"))
    )
    (net (code "50") (name "Net-(U2-P3.7{slash}TB2.2)") (class "Default")
      (node (ref "R21") (pin "1") (pinfunction "1_1") (pintype "passive"))
      (node (ref "U2") (pin "P$29") (pinfunction "P3.7/TB2.2_P$29") (pintype "bidirectional"))
    )
    (net (code "51") (name "Net-(U2-PJ.1{slash}TDI{slash}TCLK{slash}TB1OUTH{slash}MCLK{slash}CD7)") (class "Default")
      (node (ref "JP9") (pin "1") (pinfunction "1_1") (pintype "passive"))
      (node (ref "U2") (pin "P$16") (pinfunction "PJ.1/TDI/TCLK/TB1OUTH/MCLK/CD7_P$16") (pintype "bidirectional"))
    )
    (net (code "52") (name "Net-(U2-PJ.2{slash}TMS{slash}TB2OUTH{slash}ACLK{slash}CD8)") (class "Default")
      (node (ref "JP9") (pin "2") (pinfunction "2_2") (pintype "passive"))
      (node (ref "U2") (pin "P$17") (pinfunction "PJ.2/TMS/TB2OUTH/ACLK/CD8_P$17") (pintype "bidirectional"))
    )
    (net (code "53") (name "Net-(U2-PJ.3{slash}TCK{slash}CD9)") (class "Default")
      (node (ref "JP9") (pin "3") (pinfunction "3_3") (pintype "passive"))
      (node (ref "U2") (pin "P$18") (pinfunction "PJ.3/TCK/CD9_P$18") (pintype "bidirectional"))
    )
    (net (code "54") (name "Net-(U2-PJ.4{slash}XIN)") (class "Default")
      (node (ref "C23") (pin "1") (pinfunction "1_1") (pintype "passive"))
      (node (ref "Q5") (pin "2") (pinfunction "2_2") (pintype "passive"))
      (node (ref "U2") (pin "P$1") (pinfunction "PJ.4/XIN_P$1") (pintype "bidirectional"))
    )
    (net (code "55") (name "Net-(U2-PJ.5{slash}XOUT)") (class "Default")
      (node (ref "C24") (pin "1") (pinfunction "1_1") (pintype "passive"))
      (node (ref "Q5") (pin "1") (pinfunction "1_1") (pintype "passive"))
      (node (ref "U2") (pin "P$2") (pinfunction "PJ.5/XOUT_P$2") (pintype "bidirectional"))
    )
    (net (code "56") (name "Net-(U2-VCORE)") (class "Default")
      (node (ref "C17") (pin "1") (pinfunction "1_1") (pintype "passive"))
      (node (ref "U2") (pin "P$32") (pinfunction "VCORE_P$32") (pintype "bidirectional"))
    )
    (net (code "57") (name "Net-(Z1-P$2)") (class "Default")
      (node (ref "JP2") (pin "2") (pinfunction "2_2") (pintype "passive"))
      (node (ref "Z1") (pin "P$1") (pinfunction "P$2_P$1") (pintype "bidirectional"))
    )
    (net (code "58") (name "Net-(Z2-P$2)") (class "Default")
      (node (ref "Z1") (pin "P$3") (pinfunction "P$3_P$3") (pintype "bidirectional"))
      (node (ref "Z2") (pin "P$3") (pinfunction "P$2_P$3") (pintype "bidirectional"))
    )
    (net (code "59") (name "POSHV") (class "Default")
      (node (ref "JP6") (pin "46") (pinfunction "46_46") (pintype "passive"))
      (node (ref "R22") (pin "2") (pinfunction "2_2") (pintype "passive"))
    )
    (net (code "60") (name "REG_SHDN") (class "Default")
      (node (ref "PAD5") (pin "1") (pinfunction "P_1") (pintype "passive"))
      (node (ref "R1") (pin "1") (pinfunction "1_1") (pintype "passive"))
      (node (ref "U1") (pin "4") (pinfunction "~{SD}_4") (pintype "input"))
      (node (ref "U2") (pin "P$15") (pinfunction "PJ.0/TDO/TB0OUTH/SMCLK/CD6_P$15") (pintype "bidirectional"))
    )
    (net (code "61") (name "RST") (class "Default")
      (node (ref "C25") (pin "1") (pinfunction "1_1") (pintype "passive"))
      (node (ref "JP3") (pin "4") (pinfunction "4_4") (pintype "passive"))
      (node (ref "R10") (pin "1") (pinfunction "1_1") (pintype "passive"))
      (node (ref "U2") (pin "P$22") (pinfunction "RST/NMI/SBWTDIO_P$22") (pintype "bidirectional"))
    )
    (net (code "62") (name "RXD") (class "Default")
      (node (ref "JP3") (pin "3") (pinfunction "3_3") (pintype "passive"))
      (node (ref "U2") (pin "P$24") (pinfunction "P2.1/TB2.1/UCA0RXD/UCA0SOMI/TB0.0_P$24") (pintype "bidirectional"))
    )
    (net (code "63") (name "SCL") (class "Default")
      (node (ref "JP6") (pin "43") (pinfunction "43_43") (pintype "passive"))
      (node (ref "JP6") (pin "44") (pinfunction "44_44") (pintype "passive"))
      (node (ref "R20") (pin "2") (pinfunction "2_2") (pintype "passive"))
    )
    (net (code "64") (name "SDA") (class "Default")
      (node (ref "JP6") (pin "41") (pinfunction "41_41") (pintype "passive"))
      (node (ref "JP6") (pin "42") (pinfunction "42_42") (pintype "passive"))
      (node (ref "R19") (pin "2") (pinfunction "2_2") (pintype "passive"))
    )
    (net (code "65") (name "TEST") (class "Default")
      (node (ref "JP3") (pin "5") (pinfunction "5_5") (pintype "passive"))
      (node (ref "U2") (pin "P$21") (pinfunction "TEST/SBWTCK_P$21") (pintype "bidirectional"))
    )
    (net (code "66") (name "TXD") (class "Default")
      (node (ref "JP3") (pin "2") (pinfunction "2_2") (pintype "passive"))
      (node (ref "U2") (pin "P$23") (pinfunction "P2.0/TB2.0/UCA0TXD/UCA0SIMO/TB0CLK/ACLK_P$23") (pintype "bidirectional"))
    )
    (net (code "67") (name "V+") (class "Default")
      (node (ref "C10") (pin "1") (pinfunction "1_1") (pintype "passive"))
      (node (ref "C12") (pin "1") (pinfunction "1_1") (pintype "passive"))
      (node (ref "C14") (pin "1") (pinfunction "1_1") (pintype "passive"))
      (node (ref "C5") (pin "2") (pinfunction "2_2") (pintype "passive"))
      (node (ref "C6") (pin "1") (pinfunction "1_1") (pintype "passive"))
      (node (ref "C8") (pin "1") (pinfunction "1_1") (pintype "passive"))
      (node (ref "D1") (pin "1") (pinfunction "C_1") (pintype "passive"))
      (node (ref "D2") (pin "C") (pinfunction "C_C") (pintype "passive"))
      (node (ref "D3") (pin "C") (pinfunction "C_C") (pintype "passive"))
      (node (ref "JP12") (pin "1") (pinfunction "1_1") (pintype "passive"))
      (node (ref "Q1") (pin "3") (pinfunction "P-S_3") (pintype "passive"))
      (node (ref "Q2") (pin "3") (pinfunction "P-S_3") (pintype "passive"))
      (node (ref "R2") (pin "1") (pinfunction "1_1") (pintype "passive"))
      (node (ref "R6") (pin "2") (pinfunction "2_2") (pintype "passive"))
      (node (ref "R7") (pin "2") (pinfunction "2_2") (pintype "passive"))
    )
    (net (code "68") (name "VCC") (class "Default")
      (node (ref "C20") (pin "1") (pinfunction "1_1") (pintype "passive"))
      (node (ref "C22") (pin "1") (pinfunction "1_1") (pintype "passive"))
      (node (ref "C27") (pin "P$3") (pinfunction "P$3_P$3") (pintype "bidirectional"))
      (node (ref "JP3") (pin "1") (pinfunction "1_1") (pintype "passive"))
      (node (ref "JP4") (pin "3") (pinfunction "3_3") (pintype "passive"))
      (node (ref "JP5") (pin "1") (pinfunction "1_1") (pintype "passive"))
      (node (ref "JP9") (pin "5") (pinfunction "5_5") (pintype "passive"))
      (node (ref "Q8") (pin "1") (pinfunction "G_1") (pintype "passive"))
      (node (ref "Q9") (pin "1") (pinfunction "G_1") (pintype "passive"))
      (node (ref "R10") (pin "2") (pinfunction "2_2") (pintype "passive"))
      (node (ref "R14") (pin "2") (pinfunction "2_2") (pintype "passive"))
      (node (ref "R16") (pin "2") (pinfunction "2_2") (pintype "passive"))
      (node (ref "R23") (pin "1") (pinfunction "1_1") (pintype "passive"))
      (node (ref "R24") (pin "1") (pinfunction "1_1") (pintype "passive"))
      (node (ref "U2") (pin "P$34") (pinfunction "DVCC_P$34") (pintype "bidirectional"))
      (node (ref "U2") (pin "P$4") (pinfunction "AVCC_P$4") (pintype "bidirectional"))
    )
    (net (code "69") (name "unconnected-(JP6-Pad1)") (class "Default")
      (node (ref "JP6") (pin "1") (pinfunction "1_1") (pintype "passive"))
    )
    (net (code "70") (name "unconnected-(JP6-Pad2)") (class "Default")
      (node (ref "JP6") (pin "2") (pinfunction "2_2") (pintype "passive"))
    )
    (net (code "71") (name "unconnected-(JP6-Pad3)") (class "Default")
      (node (ref "JP6") (pin "3") (pinfunction "3_3") (pintype "passive"))
    )
    (net (code "72") (name "unconnected-(JP6-Pad4)") (class "Default")
      (node (ref "JP6") (pin "4") (pinfunction "4_4") (pintype "passive"))
    )
    (net (code "73") (name "unconnected-(JP6-Pad7)") (class "Default")
      (node (ref "JP6") (pin "7") (pinfunction "7_7") (pintype "passive"))
    )
    (net (code "74") (name "unconnected-(JP6-Pad8)") (class "Default")
      (node (ref "JP6") (pin "8") (pinfunction "8_8") (pintype "passive"))
    )
    (net (code "75") (name "unconnected-(JP6-Pad9)") (class "Default")
      (node (ref "JP6") (pin "9") (pinfunction "9_9") (pintype "passive"))
    )
    (net (code "76") (name "unconnected-(JP6-Pad10)") (class "Default")
      (node (ref "JP6") (pin "10") (pinfunction "10_10") (pintype "passive"))
    )
    (net (code "77") (name "unconnected-(JP6-Pad11)") (class "Default")
      (node (ref "JP6") (pin "11") (pinfunction "11_11") (pintype "passive"))
    )
    (net (code "78") (name "unconnected-(JP6-Pad12)") (class "Default")
      (node (ref "JP6") (pin "12") (pinfunction "12_12") (pintype "passive"))
    )
    (net (code "79") (name "unconnected-(JP6-Pad13)") (class "Default")
      (node (ref "JP6") (pin "13") (pinfunction "13_13") (pintype "passive"))
    )
    (net (code "80") (name "unconnected-(JP6-Pad14)") (class "Default")
      (node (ref "JP6") (pin "14") (pinfunction "14_14") (pintype "passive"))
    )
    (net (code "81") (name "unconnected-(JP6-Pad15)") (class "Default")
      (node (ref "JP6") (pin "15") (pinfunction "15_15") (pintype "passive"))
    )
    (net (code "82") (name "unconnected-(JP6-Pad16)") (class "Default")
      (node (ref "JP6") (pin "16") (pinfunction "16_16") (pintype "passive"))
    )
    (net (code "83") (name "unconnected-(JP6-Pad17)") (class "Default")
      (node (ref "JP6") (pin "17") (pinfunction "17_17") (pintype "passive"))
    )
    (net (code "84") (name "unconnected-(JP6-Pad18)") (class "Default")
      (node (ref "JP6") (pin "18") (pinfunction "18_18") (pintype "passive"))
    )
    (net (code "85") (name "unconnected-(JP6-Pad19)") (class "Default")
      (node (ref "JP6") (pin "19") (pinfunction "19_19") (pintype "passive"))
    )
    (net (code "86") (name "unconnected-(JP6-Pad20)") (class "Default")
      (node (ref "JP6") (pin "20") (pinfunction "20_20") (pintype "passive"))
    )
    (net (code "87") (name "unconnected-(JP6-Pad21)") (class "Default")
      (node (ref "JP6") (pin "21") (pinfunction "21_21") (pintype "passive"))
    )
    (net (code "88") (name "unconnected-(JP6-Pad22)") (class "Default")
      (node (ref "JP6") (pin "22") (pinfunction "22_22") (pintype "passive"))
    )
    (net (code "89") (name "unconnected-(JP6-Pad23)") (class "Default")
      (node (ref "JP6") (pin "23") (pinfunction "23_23") (pintype "passive"))
    )
    (net (code "90") (name "unconnected-(JP6-Pad24)") (class "Default")
      (node (ref "JP6") (pin "24") (pinfunction "24_24") (pintype "passive"))
    )
    (net (code "91") (name "unconnected-(JP6-Pad26)") (class "Default")
      (node (ref "JP6") (pin "26") (pinfunction "26_26") (pintype "passive"))
    )
    (net (code "92") (name "unconnected-(JP6-Pad28)") (class "Default")
      (node (ref "JP6") (pin "28") (pinfunction "28_28") (pintype "passive"))
    )
    (net (code "93") (name "unconnected-(JP6-Pad30)") (class "Default")
      (node (ref "JP6") (pin "30") (pinfunction "30_30") (pintype "passive"))
    )
    (net (code "94") (name "unconnected-(JP6-Pad31)") (class "Default")
      (node (ref "JP6") (pin "31") (pinfunction "31_31") (pintype "passive"))
    )
    (net (code "95") (name "unconnected-(JP6-Pad32)") (class "Default")
      (node (ref "JP6") (pin "32") (pinfunction "32_32") (pintype "passive"))
    )
    (net (code "96") (name "unconnected-(JP6-Pad35)") (class "Default")
      (node (ref "JP6") (pin "35") (pinfunction "35_35") (pintype "passive"))
    )
    (net (code "97") (name "unconnected-(JP6-Pad36)") (class "Default")
      (node (ref "JP6") (pin "36") (pinfunction "36_36") (pintype "passive"))
    )
    (net (code "98") (name "unconnected-(JP6-Pad37)") (class "Default")
      (node (ref "JP6") (pin "37") (pinfunction "37_37") (pintype "passive"))
    )
    (net (code "99") (name "unconnected-(JP6-Pad38)") (class "Default")
      (node (ref "JP6") (pin "38") (pinfunction "38_38") (pintype "passive"))
    )
    (net (code "100") (name "unconnected-(U2-P2.6{slash}TB1.0{slash}UCA1RXD{slash}UCA1SOMI-PadP$20)") (class "Default")
      (node (ref "U2") (pin "P$20") (pinfunction "P2.6/TB1.0/UCA1RXD/UCA1SOMI_P$20") (pintype "bidirectional"))
    )
    (net (code "101") (name "unconnected-(U2-P3.1{slash}A13*{slash}CD13-PadP$9)") (class "Default")
      (node (ref "U2") (pin "P$9") (pinfunction "P3.1/A13*/CD13_P$9") (pintype "bidirectional"))
    )
    (net (code "102") (name "unconnected-(U2-P3.3{slash}A15*{slash}CD15-PadP$11)") (class "Default")
      (node (ref "U2") (pin "P$11") (pinfunction "P3.3/A15*/CD15_P$11") (pintype "bidirectional"))
    )
    (net (code "103") (name "unconnected-(U2-P3.6{slash}TB2.1{slash}TB1CLK-PadP$28)") (class "Default")
      (node (ref "U2") (pin "P$28") (pinfunction "P3.6/TB2.1/TB1CLK_P$28") (pintype "bidirectional"))
    )
  )
)
